# 1.net
KiCad netlist of a schematic drawn in Altium Designer
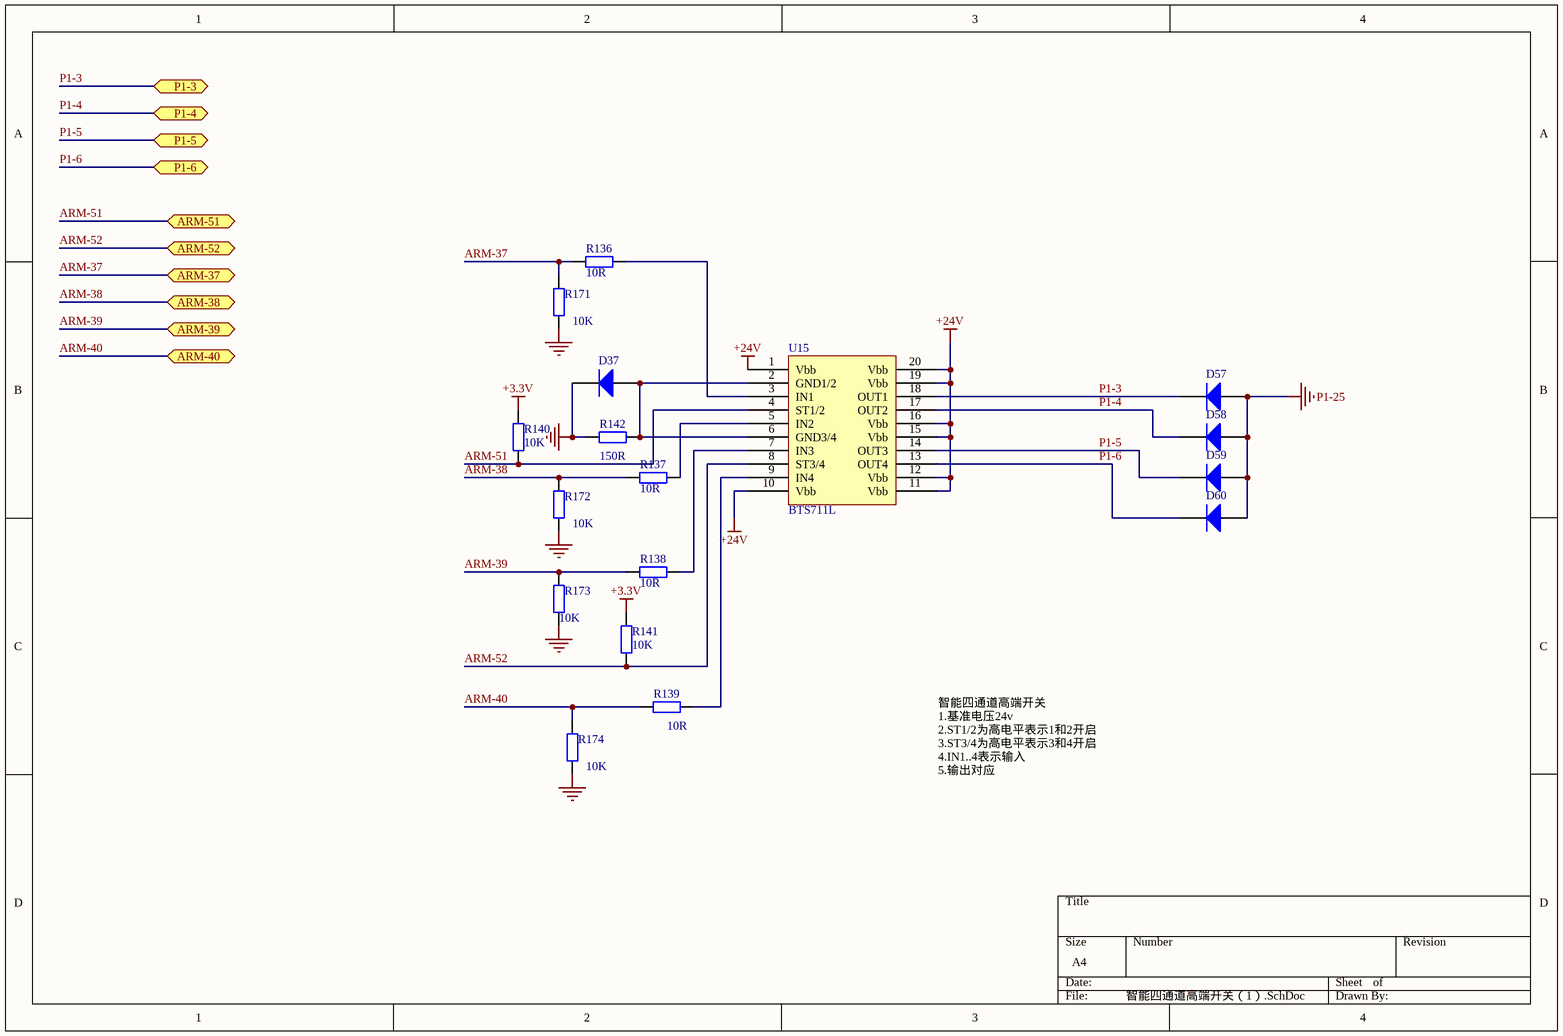
[diagram p0: 智能四通道高端开关（1）.SchDoc]

(export (version "E")
  (design (tool "Eeschema 10.0.6"))
  (components
    (comp (ref "D37")
      (value "Diode 1N4007")
      (footprint "SOD123")
      (description "1 Amp General Purpose Rectifier")
      (fields (field (name "PUBLISHER") "Altium Limited"))
      (libsource (lib "Miscellaneous Devices") (part "Diode 1N4007"))
    )
    (comp (ref "D57")
      (value "Diode 1N4007")
      (footprint "DO214AB")
      (description "1 Amp General Purpose Rectifier")
      (fields (field (name "PUBLISHER") "Altium Limited"))
      (libsource (lib "Miscellaneous Devices") (part "Diode 1N4007"))
    )
    (comp (ref "D58")
      (value "Diode 1N4007")
      (footprint "DO214AB")
      (description "1 Amp General Purpose Rectifier")
      (fields (field (name "PUBLISHER") "Altium Limited"))
      (libsource (lib "Miscellaneous Devices") (part "Diode 1N4007"))
    )
    (comp (ref "D59")
      (value "Diode 1N4007")
      (footprint "DO214AB")
      (description "1 Amp General Purpose Rectifier")
      (fields (field (name "PUBLISHER") "Altium Limited"))
      (libsource (lib "Miscellaneous Devices") (part "Diode 1N4007"))
    )
    (comp (ref "D60")
      (value "Diode 1N4007")
      (footprint "DO214AB")
      (description "1 Amp General Purpose Rectifier")
      (fields (field (name "PUBLISHER") "Altium Limited"))
      (libsource (lib "Miscellaneous Devices") (part "Diode 1N4007"))
    )
    (comp (ref "R136")
      (value "10R")
      (footprint "采集板3.0增加1路模拟量2:R0805")
      (description "Resistor")
      (fields (field (name "Comment") "Res2") (field (name "PUBLISHER") "Altium Limited"))
      (libsource (lib "Miscellaneous Devices") (part "Res2"))
    )
    (comp (ref "R137")
      (value "10R")
      (footprint "采集板3.0增加1路模拟量2:R0805")
      (description "Resistor")
      (fields (field (name "Comment") "Res2") (field (name "PUBLISHER") "Altium Limited"))
      (libsource (lib "Miscellaneous Devices") (part "Res2"))
    )
    (comp (ref "R138")
      (value "10R")
      (footprint "采集板3.0增加1路模拟量2:R0805")
      (description "Resistor")
      (fields (field (name "Comment") "Res2") (field (name "PUBLISHER") "Altium Limited"))
      (libsource (lib "Miscellaneous Devices") (part "Res2"))
    )
    (comp (ref "R139")
      (value "10R")
      (footprint "采集板3.0增加1路模拟量2:R0805")
      (description "Resistor")
      (fields (field (name "Comment") "Res2") (field (name "PUBLISHER") "Altium Limited"))
      (libsource (lib "Miscellaneous Devices") (part "Res2"))
    )
    (comp (ref "R140")
      (value "10K")
      (footprint "采集板3.0增加1路模拟量2:R0805")
      (description "Resistor")
      (fields (field (name "Comment") "Res2") (field (name "PUBLISHER") "Altium Limited"))
      (libsource (lib "") (part "Res2_3"))
    )
    (comp (ref "R141")
      (value "10K")
      (footprint "采集板3.0增加1路模拟量2:R0805")
      (description "Resistor")
      (fields (field (name "Comment") "Res2") (field (name "PUBLISHER") "Altium Limited"))
      (libsource (lib "") (part "Res2_3"))
    )
    (comp (ref "R142")
      (value "150R")
      (footprint "R0805")
      (description "Resistor")
      (fields (field (name "Comment") "Res2") (field (name "PUBLISHER") "Altium Limited"))
      (libsource (lib "") (part "Res2_2"))
    )
    (comp (ref "R171")
      (value "10K")
      (footprint "采集板3.0增加1路模拟量2:R0805")
      (description "Resistor")
      (fields (field (name "Comment") "Res2") (field (name "PUBLISHER") "Altium Limited"))
      (libsource (lib "") (part "Res2_1"))
    )
    (comp (ref "R172")
      (value "10K")
      (footprint "采集板3.0增加1路模拟量2:R0805")
      (description "Resistor")
      (fields (field (name "Comment") "Res2") (field (name "PUBLISHER") "Altium Limited"))
      (libsource (lib "") (part "Res2_1"))
    )
    (comp (ref "R173")
      (value "10K")
      (footprint "采集板3.0增加1路模拟量2:R0805")
      (description "Resistor")
      (fields (field (name "Comment") "Res2") (field (name "PUBLISHER") "Altium Limited"))
      (libsource (lib "") (part "Res2_1"))
    )
    (comp (ref "R174")
      (value "10K")
      (footprint "采集板3.0增加1路模拟量2:R0805")
      (description "Resistor")
      (fields (field (name "Comment") "Res2") (field (name "PUBLISHER") "Altium Limited"))
      (libsource (lib "") (part "Res2_1"))
    )
    (comp (ref "U15")
      (value "BTS711L")
      (footprint "SOP-20")
      (libsource (lib "BTS711L1") (part "Component_1"))
    )
  )
  (nets
    (net (code "1") (name "+3.3V") (class "Default")
      (node (ref "R140") (pin "1") (pinfunction "1_1") (pintype "passive"))
      (node (ref "R141") (pin "1") (pinfunction "1_1") (pintype "passive"))
    )
    (net (code "2") (name "+24V") (class "Default")
      (node (ref "U15") (pin "1") (pinfunction "Vbb_1") (pintype "passive"))
      (node (ref "U15") (pin "10") (pinfunction "Vbb_10") (pintype "passive"))
      (node (ref "U15") (pin "11") (pinfunction "Vbb_11") (pintype "passive"))
      (node (ref "U15") (pin "12") (pinfunction "Vbb_12") (pintype "passive"))
      (node (ref "U15") (pin "15") (pinfunction "Vbb_15") (pintype "passive"))
      (node (ref "U15") (pin "16") (pinfunction "Vbb_16") (pintype "passive"))
      (node (ref "U15") (pin "19") (pinfunction "Vbb_19") (pintype "passive"))
      (node (ref "U15") (pin "20") (pinfunction "Vbb_20") (pintype "passive"))
    )
    (net (code "3") (name "/ARM-37") (class "Default")
      (node (ref "R136") (pin "2") (pinfunction "2_2") (pintype "passive"))
      (node (ref "R171") (pin "2") (pinfunction "2_2") (pintype "passive"))
    )
    (net (code "4") (name "/ARM-38") (class "Default")
      (node (ref "R137") (pin "2") (pinfunction "2_2") (pintype "passive"))
      (node (ref "R172") (pin "2") (pinfunction "2_2") (pintype "passive"))
    )
    (net (code "5") (name "/ARM-39") (class "Default")
      (node (ref "R138") (pin "2") (pinfunction "2_2") (pintype "passive"))
      (node (ref "R173") (pin "2") (pinfunction "2_2") (pintype "passive"))
    )
    (net (code "6") (name "/ARM-40") (class "Default")
      (node (ref "R139") (pin "2") (pinfunction "2_2") (pintype "passive"))
      (node (ref "R174") (pin "2") (pinfunction "2_2") (pintype "passive"))
    )
    (net (code "7") (name "/ARM-51") (class "Default")
      (node (ref "R140") (pin "2") (pinfunction "2_2") (pintype "passive"))
      (node (ref "U15") (pin "4") (pinfunction "ST1/2_4") (pintype "passive"))
    )
    (net (code "8") (name "/ARM-52") (class "Default")
      (node (ref "R141") (pin "2") (pinfunction "2_2") (pintype "passive"))
      (node (ref "U15") (pin "8") (pinfunction "ST3/4_8") (pintype "passive"))
    )
    (net (code "9") (name "/P1-3") (class "Default")
      (node (ref "D57") (pin "2") (pinfunction "K_2") (pintype "passive"))
      (node (ref "U15") (pin "18") (pinfunction "OUT1_18") (pintype "passive"))
    )
    (net (code "10") (name "/P1-4") (class "Default")
      (node (ref "D58") (pin "2") (pinfunction "K_2") (pintype "passive"))
      (node (ref "U15") (pin "17") (pinfunction "OUT2_17") (pintype "passive"))
    )
    (net (code "11") (name "/P1-5") (class "Default")
      (node (ref "D59") (pin "2") (pinfunction "K_2") (pintype "passive"))
      (node (ref "U15") (pin "14") (pinfunction "OUT3_14") (pintype "passive"))
    )
    (net (code "12") (name "/P1-6") (class "Default")
      (node (ref "D60") (pin "2") (pinfunction "K_2") (pintype "passive"))
      (node (ref "U15") (pin "13") (pinfunction "OUT4_13") (pintype "passive"))
    )
    (net (code "13") (name "GND") (class "Default")
      (node (ref "D37") (pin "2") (pinfunction "K_2") (pintype "passive"))
      (node (ref "R142") (pin "1") (pinfunction "1_1") (pintype "passive"))
      (node (ref "R171") (pin "1") (pinfunction "1_1") (pintype "passive"))
      (node (ref "R172") (pin "1") (pinfunction "1_1") (pintype "passive"))
      (node (ref "R173") (pin "1") (pinfunction "1_1") (pintype "passive"))
      (node (ref "R174") (pin "1") (pinfunction "1_1") (pintype "passive"))
    )
    (net (code "14") (name "Net-(D37-A)") (class "Default")
      (node (ref "D37") (pin "1") (pinfunction "A_1") (pintype "passive"))
      (node (ref "R142") (pin "2") (pinfunction "2_2") (pintype "passive"))
      (node (ref "U15") (pin "2") (pinfunction "GND1/2_2") (pintype "passive"))
      (node (ref "U15") (pin "6") (pinfunction "GND3/4_6") (pintype "passive"))
    )
    (net (code "15") (name "Net-(U15-IN1)") (class "Default")
      (node (ref "R136") (pin "1") (pinfunction "1_1") (pintype "passive"))
      (node (ref "U15") (pin "3") (pinfunction "IN1_3") (pintype "passive"))
    )
    (net (code "16") (name "Net-(U15-IN2)") (class "Default")
      (node (ref "R137") (pin "1") (pinfunction "1_1") (pintype "passive"))
      (node (ref "U15") (pin "5") (pinfunction "IN2_5") (pintype "passive"))
    )
    (net (code "17") (name "Net-(U15-IN3)") (class "Default")
      (node (ref "R138") (pin "1") (pinfunction "1_1") (pintype "passive"))
      (node (ref "U15") (pin "7") (pinfunction "IN3_7") (pintype "passive"))
    )
    (net (code "18") (name "Net-(U15-IN4)") (class "Default")
      (node (ref "R139") (pin "1") (pinfunction "1_1") (pintype "passive"))
      (node (ref "U15") (pin "9") (pinfunction "IN4_9") (pintype "passive"))
    )
    (net (code "19") (name "P1-25") (class "Default")
      (node (ref "D57") (pin "1") (pinfunction "A_1") (pintype "passive"))
      (node (ref "D58") (pin "1") (pinfunction "A_1") (pintype "passive"))
      (node (ref "D59") (pin "1") (pinfunction "A_1") (pintype "passive"))
      (node (ref "D60") (pin "1") (pinfunction "A_1") (pintype "passive"))
    )
  )
)
